# divchrono-amplifier.net
KiCad netlist of a schematic drawn in EAGLE
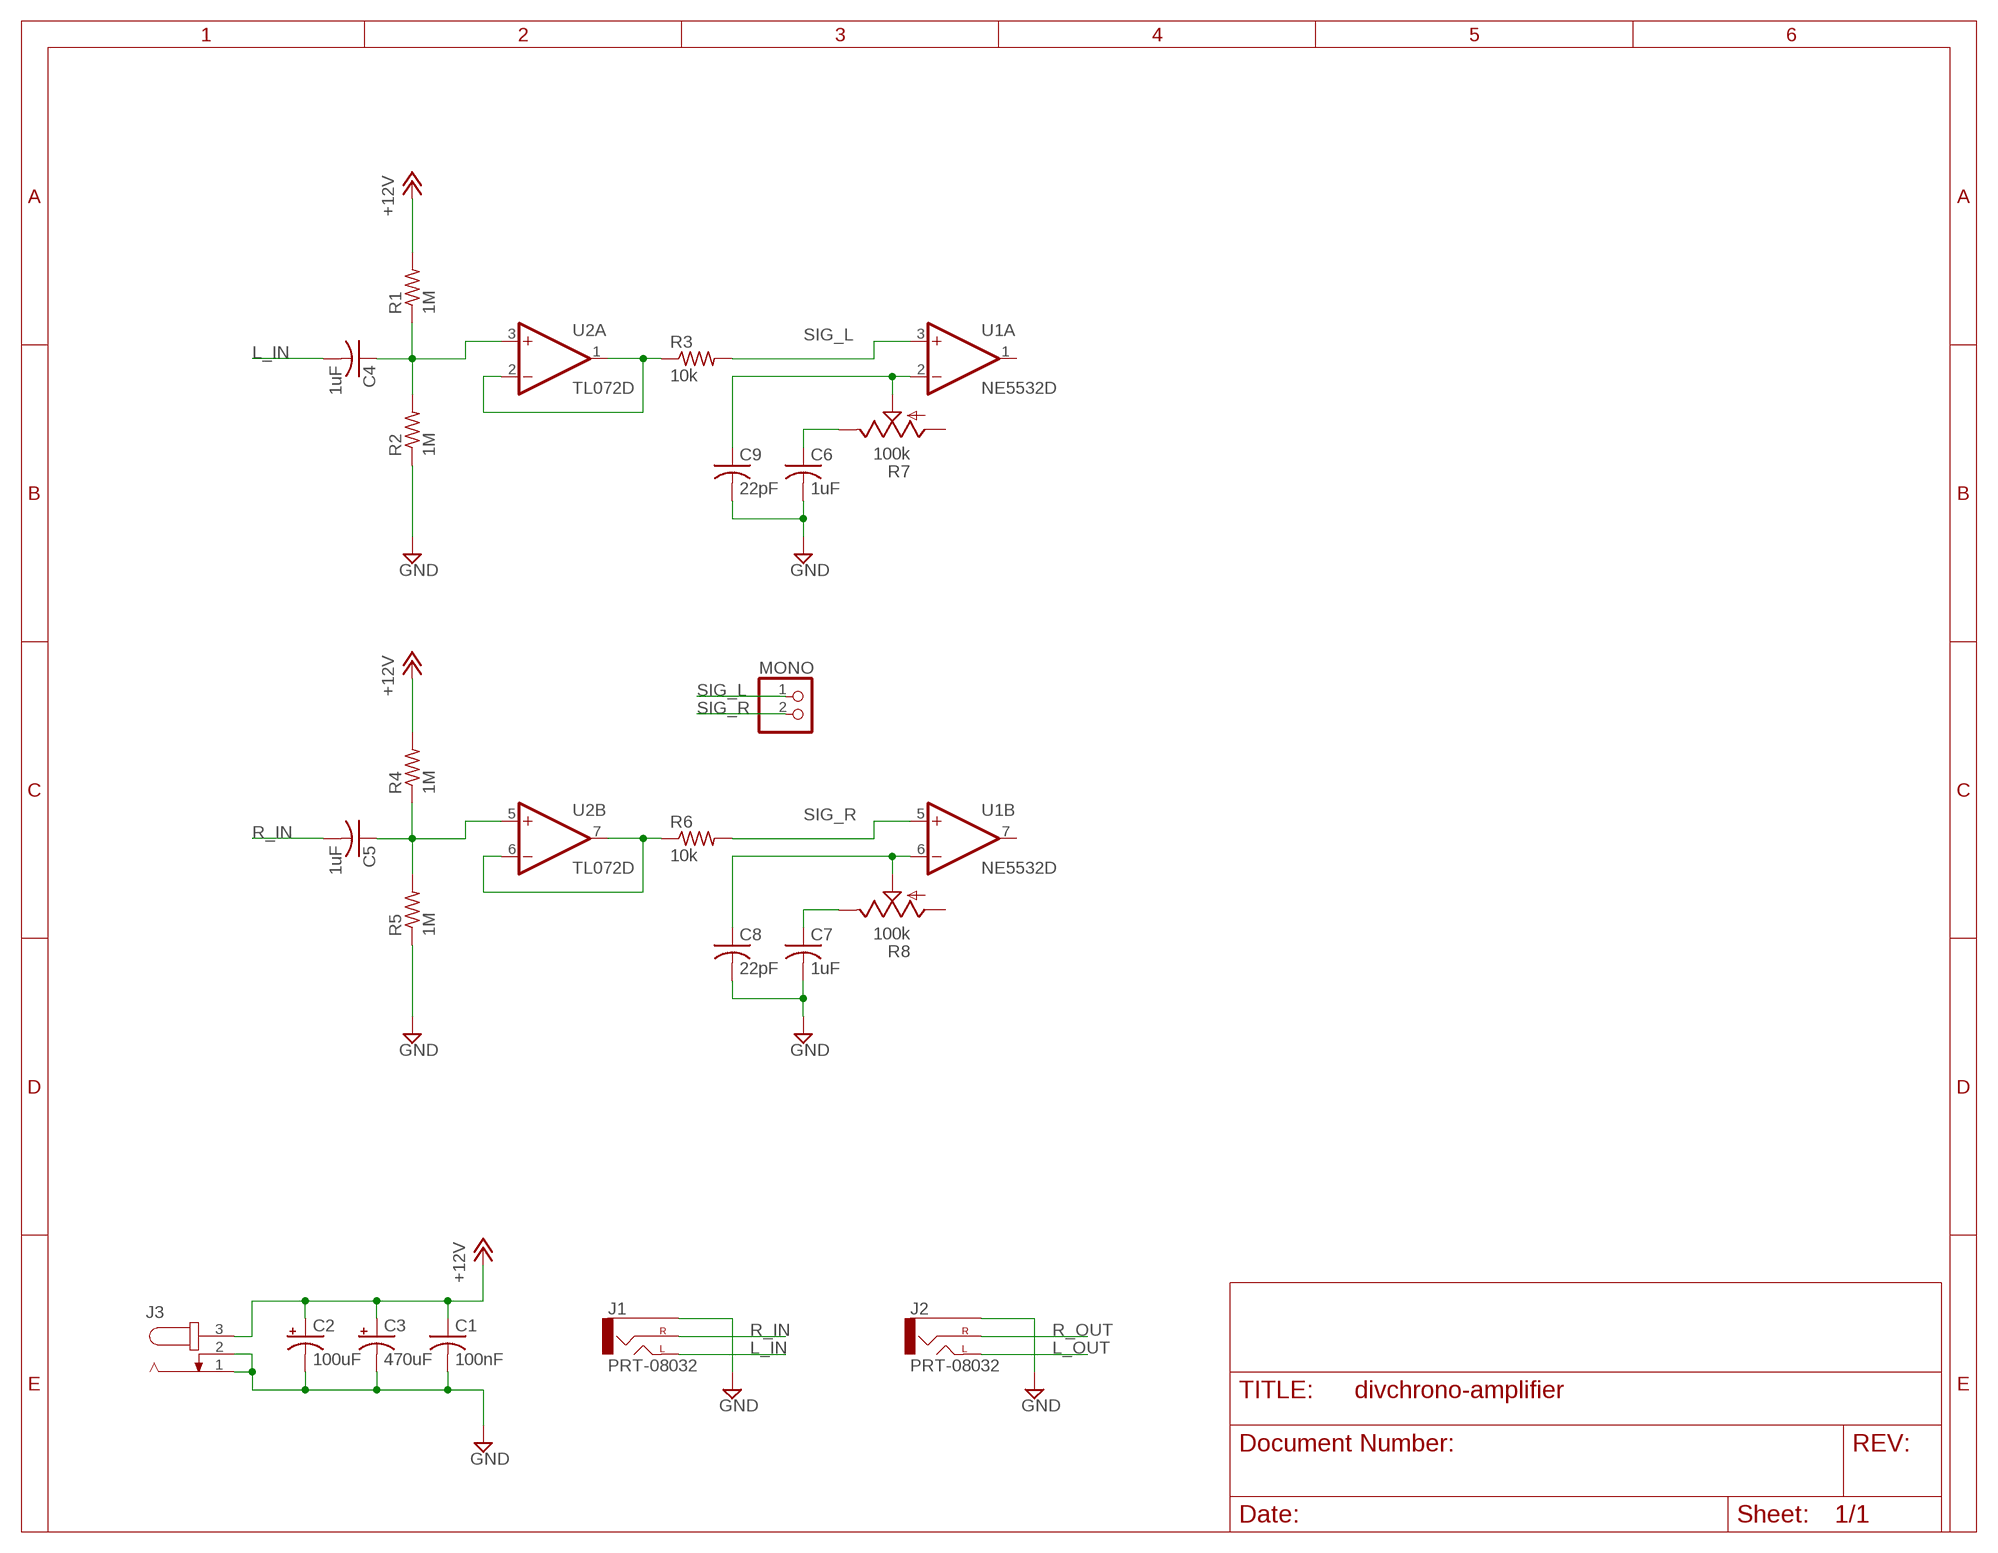
[diagram p0: schematic, sheet 1]

(export (version "E")
  (design (tool "Eeschema 10.0.6"))
  (components
    (comp (ref "C1")
      (value "100nF")
      (footprint "eagle-import:C1206")
      (libsource (lib "eagle-import") (part "C-USC1206"))
    )
    (comp (ref "C2")
      (value "100uF")
      (footprint "eagle-import:E2,5-6")
      (libsource (lib "eagle-import") (part "CPOL-USE2.5-6"))
    )
    (comp (ref "C3")
      (value "470uF")
      (footprint "eagle-import:E2,5-6")
      (libsource (lib "eagle-import") (part "CPOL-USE2.5-6"))
    )
    (comp (ref "C4")
      (value "1uF")
      (footprint "eagle-import:C1206")
      (libsource (lib "eagle-import") (part "C-USC1206"))
    )
    (comp (ref "C5")
      (value "1uF")
      (footprint "eagle-import:C1206")
      (libsource (lib "eagle-import") (part "C-USC1206"))
    )
    (comp (ref "C6")
      (value "1uF")
      (footprint "eagle-import:C1206")
      (libsource (lib "eagle-import") (part "C-USC1206"))
    )
    (comp (ref "C7")
      (value "1uF")
      (footprint "eagle-import:C1206")
      (libsource (lib "eagle-import") (part "C-USC1206"))
    )
    (comp (ref "C8")
      (value "22pF")
      (footprint "eagle-import:C1206")
      (libsource (lib "eagle-import") (part "C-USC1206"))
    )
    (comp (ref "C9")
      (value "22pF")
      (footprint "eagle-import:C1206")
      (libsource (lib "eagle-import") (part "C-USC1206"))
    )
    (comp (ref "J1")
      (value "PRT-08032")
      (footprint "eagle-import:AUDIO-JACK")
      (libsource (lib "eagle-import") (part "AUDIO-JACKPTH"))
    )
    (comp (ref "J2")
      (value "PRT-08032")
      (footprint "eagle-import:AUDIO-JACK")
      (libsource (lib "eagle-import") (part "AUDIO-JACKPTH"))
    )
    (comp (ref "J3")
      (value "JACK-PLUG0")
      (footprint "eagle-import:SPC4077")
      (libsource (lib "eagle-import") (part "JACK-PLUG0"))
    )
    (comp (ref "MONO")
      (value "PINHD-1X2")
      (footprint "eagle-import:1X02")
      (libsource (lib "eagle-import") (part "PINHD-1X2"))
    )
    (comp (ref "R1")
      (value "1M")
      (footprint "eagle-import:R1206")
      (libsource (lib "eagle-import") (part "R-US_R1206"))
    )
    (comp (ref "R2")
      (value "1M")
      (footprint "eagle-import:R1206")
      (libsource (lib "eagle-import") (part "R-US_R1206"))
    )
    (comp (ref "R3")
      (value "10k")
      (footprint "eagle-import:R1206")
      (libsource (lib "eagle-import") (part "R-US_R1206"))
    )
    (comp (ref "R4")
      (value "1M")
      (footprint "eagle-import:R1206")
      (libsource (lib "eagle-import") (part "R-US_R1206"))
    )
    (comp (ref "R5")
      (value "1M")
      (footprint "eagle-import:R1206")
      (libsource (lib "eagle-import") (part "R-US_R1206"))
    )
    (comp (ref "R6")
      (value "10k")
      (footprint "eagle-import:R1206")
      (libsource (lib "eagle-import") (part "R-US_R1206"))
    )
    (comp (ref "R7")
      (value "100k")
      (footprint "eagle-import:CT6")
      (libsource (lib "eagle-import") (part "TRIM_US-CT6"))
    )
    (comp (ref "R8")
      (value "100k")
      (footprint "eagle-import:CT6")
      (libsource (lib "eagle-import") (part "TRIM_US-CT6"))
    )
    (comp (ref "U1")
      (value "NE5532D")
      (footprint "eagle-import:SO08")
      (libsource (lib "eagle-import") (part "NE5532D"))
    )
    (comp (ref "U2")
      (value "TL072D")
      (footprint "eagle-import:SO08")
      (libsource (lib "eagle-import") (part "TL072D"))
    )
  )
  (nets
    (net (code "1") (name "+12V") (class "Default")
      (node (ref "C1") (pin "1") (pinfunction "1_1") (pintype "passive"))
      (node (ref "C2") (pin "+") (pinfunction "+_+") (pintype "passive"))
      (node (ref "C3") (pin "+") (pinfunction "+_+") (pintype "passive"))
      (node (ref "J3") (pin "3") (pinfunction "3_3") (pintype "passive"))
      (node (ref "R1") (pin "2") (pinfunction "2_2") (pintype "passive"))
      (node (ref "R4") (pin "2") (pinfunction "2_2") (pintype "passive"))
    )
    (net (code "2") (name "/L_IN") (class "Default")
      (node (ref "C4") (pin "2") (pinfunction "2_2") (pintype "passive"))
      (node (ref "J1") (pin "TIP") (pinfunction "LEFT_TIP") (pintype "bidirectional"))
    )
    (net (code "3") (name "/L_OUT") (class "Default")
      (node (ref "J2") (pin "TIP") (pinfunction "LEFT_TIP") (pintype "bidirectional"))
    )
    (net (code "4") (name "/R_IN") (class "Default")
      (node (ref "C5") (pin "2") (pinfunction "2_2") (pintype "passive"))
      (node (ref "J1") (pin "RING") (pinfunction "RIGHT_RING") (pintype "bidirectional"))
    )
    (net (code "5") (name "/R_OUT") (class "Default")
      (node (ref "J2") (pin "RING") (pinfunction "RIGHT_RING") (pintype "bidirectional"))
    )
    (net (code "6") (name "/SIG_L") (class "Default")
      (node (ref "MONO") (pin "1") (pinfunction "1_1") (pintype "passive"))
      (node (ref "R3") (pin "2") (pinfunction "2_2") (pintype "passive"))
      (node (ref "U1") (pin "3") (pinfunction "+IN_3") (pintype "input"))
    )
    (net (code "7") (name "/SIG_R") (class "Default")
      (node (ref "MONO") (pin "2") (pinfunction "2_2") (pintype "passive"))
      (node (ref "R6") (pin "2") (pinfunction "2_2") (pintype "passive"))
      (node (ref "U1") (pin "5") (pinfunction "+IN_5") (pintype "input"))
    )
    (net (code "8") (name "GND") (class "Default")
      (node (ref "C1") (pin "2") (pinfunction "2_2") (pintype "passive"))
      (node (ref "C2") (pin "-") (pinfunction "-_-") (pintype "passive"))
      (node (ref "C3") (pin "-") (pinfunction "-_-") (pintype "passive"))
      (node (ref "C6") (pin "2") (pinfunction "2_2") (pintype "passive"))
      (node (ref "C7") (pin "2") (pinfunction "2_2") (pintype "passive"))
      (node (ref "C8") (pin "2") (pinfunction "2_2") (pintype "passive"))
      (node (ref "C9") (pin "2") (pinfunction "2_2") (pintype "passive"))
      (node (ref "J1") (pin "SLEEVE") (pinfunction "SLEEVE_SLEEVE") (pintype "bidirectional"))
      (node (ref "J2") (pin "SLEEVE") (pinfunction "SLEEVE_SLEEVE") (pintype "bidirectional"))
      (node (ref "J3") (pin "1") (pinfunction "1_1") (pintype "passive"))
      (node (ref "J3") (pin "2") (pinfunction "2_2") (pintype "passive"))
      (node (ref "R2") (pin "1") (pinfunction "1_1") (pintype "passive"))
      (node (ref "R5") (pin "1") (pinfunction "1_1") (pintype "passive"))
    )
    (net (code "9") (name "Net-(C6-Pad1)") (class "Default")
      (node (ref "C6") (pin "1") (pinfunction "1_1") (pintype "passive"))
      (node (ref "R7") (pin "E") (pinfunction "E_E") (pintype "passive"))
    )
    (net (code "10") (name "Net-(C7-Pad1)") (class "Default")
      (node (ref "C7") (pin "1") (pinfunction "1_1") (pintype "passive"))
      (node (ref "R8") (pin "E") (pinfunction "E_E") (pintype "passive"))
    )
    (net (code "11") (name "Net-(U1A--IN)") (class "Default")
      (node (ref "C9") (pin "1") (pinfunction "1_1") (pintype "passive"))
      (node (ref "R7") (pin "S") (pinfunction "S_S") (pintype "passive"))
      (node (ref "U1") (pin "2") (pinfunction "-IN_2") (pintype "input"))
    )
    (net (code "12") (name "Net-(U1B--IN)") (class "Default")
      (node (ref "C8") (pin "1") (pinfunction "1_1") (pintype "passive"))
      (node (ref "R8") (pin "S") (pinfunction "S_S") (pintype "passive"))
      (node (ref "U1") (pin "6") (pinfunction "-IN_6") (pintype "input"))
    )
    (net (code "13") (name "Net-(U2A-+IN)") (class "Default")
      (node (ref "C4") (pin "1") (pinfunction "1_1") (pintype "passive"))
      (node (ref "R1") (pin "1") (pinfunction "1_1") (pintype "passive"))
      (node (ref "R2") (pin "2") (pinfunction "2_2") (pintype "passive"))
      (node (ref "U2") (pin "3") (pinfunction "+IN_3") (pintype "input"))
    )
    (net (code "14") (name "Net-(U2A--IN)") (class "Default")
      (node (ref "R3") (pin "1") (pinfunction "1_1") (pintype "passive"))
      (node (ref "U2") (pin "1") (pinfunction "OUT_1") (pintype "output"))
      (node (ref "U2") (pin "2") (pinfunction "-IN_2") (pintype "input"))
    )
    (net (code "15") (name "Net-(U2B-+IN)") (class "Default")
      (node (ref "C5") (pin "1") (pinfunction "1_1") (pintype "passive"))
      (node (ref "R4") (pin "1") (pinfunction "1_1") (pintype "passive"))
      (node (ref "R5") (pin "2") (pinfunction "2_2") (pintype "passive"))
      (node (ref "U2") (pin "5") (pinfunction "+IN_5") (pintype "input"))
    )
    (net (code "16") (name "Net-(U2B--IN)") (class "Default")
      (node (ref "R6") (pin "1") (pinfunction "1_1") (pintype "passive"))
      (node (ref "U2") (pin "6") (pinfunction "-IN_6") (pintype "input"))
      (node (ref "U2") (pin "7") (pinfunction "OUT_7") (pintype "output"))
    )
    (net (code "17") (name "unconnected-(R7-PadA)") (class "Default")
      (node (ref "R7") (pin "A") (pinfunction "A_A") (pintype "passive"))
    )
    (net (code "18") (name "unconnected-(R8-PadA)") (class "Default")
      (node (ref "R8") (pin "A") (pinfunction "A_A") (pintype "passive"))
    )
    (net (code "19") (name "unconnected-(U1A-OUT-Pad1)") (class "Default")
      (node (ref "U1") (pin "1") (pinfunction "OUT_1") (pintype "output"))
    )
    (net (code "20") (name "unconnected-(U1B-OUT-Pad7)") (class "Default")
      (node (ref "U1") (pin "7") (pinfunction "OUT_7") (pintype "output"))
    )
  )
)
